# servoSchematic.net
KiCad netlist of a schematic drawn in EAGLE
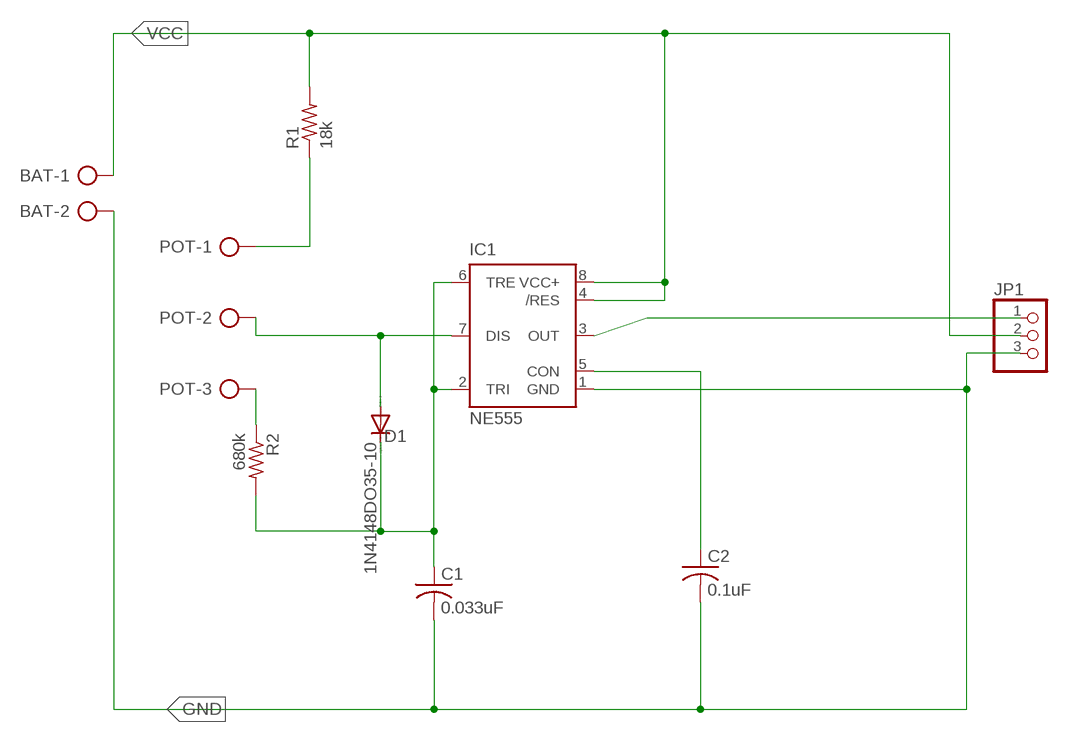
[diagram p0: schematic, sheet 1]

(export (version "E")
  (design (tool "Eeschema 10.0.6"))
  (components
    (comp (ref "BAT")
      (value "AK500/2")
      (footprint "eagle-import:AK500_2")
      (libsource (lib "eagle-import") (part "AK500/2"))
    )
    (comp (ref "C1")
      (value "0.033uF")
      (footprint "eagle-import:C025-024X044")
      (libsource (lib "eagle-import") (part "C-US025-024X044"))
    )
    (comp (ref "C2")
      (value "0.1uF")
      (footprint "eagle-import:C025-024X044")
      (libsource (lib "eagle-import") (part "C-US025-024X044"))
    )
    (comp (ref "D1")
      (value "1N4148DO35-10")
      (footprint "eagle-import:DO35-10")
      (libsource (lib "eagle-import") (part "1N4148DO35-10"))
    )
    (comp (ref "IC1")
      (value "NE555")
      (footprint "eagle-import:DIL-08")
      (fields (field (name "MF") "Arrow Electronics") (field (name "MPN") "NE555N"))
      (libsource (lib "eagle-import") (part "NE555"))
    )
    (comp (ref "JP1")
      (value "PINHD-1X3/90")
      (footprint "eagle-import:1X03_90")
      (libsource (lib "eagle-import") (part "PINHD-1X3/90"))
    )
    (comp (ref "POT")
      (value "AK500/3")
      (footprint "eagle-import:AK500_3")
      (libsource (lib "eagle-import") (part "AK500/3"))
    )
    (comp (ref "R1")
      (value "18k")
      (footprint "eagle-import:0204_7")
      (libsource (lib "eagle-import") (part "R-US_0204/7"))
    )
    (comp (ref "R2")
      (value "680k")
      (footprint "eagle-import:0204_7")
      (libsource (lib "eagle-import") (part "R-US_0204/7"))
    )
  )
  (nets
    (net (code "1") (name "GND") (class "Default")
      (node (ref "BAT") (pin "2") (pinfunction "KL_2") (pintype "passive"))
      (node (ref "C1") (pin "2") (pinfunction "2_2") (pintype "passive"))
      (node (ref "C2") (pin "2") (pinfunction "2_2") (pintype "passive"))
      (node (ref "IC1") (pin "1") (pinfunction "GND_1") (pintype "power_in"))
      (node (ref "JP1") (pin "3") (pinfunction "3_3") (pintype "passive"))
    )
    (net (code "2") (name "Net-(IC1-CON)") (class "Default")
      (node (ref "C2") (pin "1") (pinfunction "1_1") (pintype "passive"))
      (node (ref "IC1") (pin "5") (pinfunction "CON_5") (pintype "input"))
    )
    (net (code "3") (name "Net-(IC1-DIS)") (class "Default")
      (node (ref "D1") (pin "A") (pinfunction "A_A") (pintype "passive"))
      (node (ref "IC1") (pin "7") (pinfunction "DIS_7") (pintype "input"))
      (node (ref "POT") (pin "2") (pinfunction "KL_2") (pintype "passive"))
    )
    (net (code "4") (name "Net-(IC1-OUT)") (class "Default")
      (node (ref "IC1") (pin "3") (pinfunction "OUT_3") (pintype "output"))
      (node (ref "JP1") (pin "1") (pinfunction "1_1") (pintype "passive"))
    )
    (net (code "5") (name "Net-(IC1-TRE)") (class "Default")
      (node (ref "C1") (pin "1") (pinfunction "1_1") (pintype "passive"))
      (node (ref "D1") (pin "C") (pinfunction "C_C") (pintype "passive"))
      (node (ref "IC1") (pin "2") (pinfunction "TRI_2") (pintype "input"))
      (node (ref "IC1") (pin "6") (pinfunction "TRE_6") (pintype "input"))
      (node (ref "R2") (pin "2") (pinfunction "2_2") (pintype "passive"))
    )
    (net (code "6") (name "Net-(POTA-KL)") (class "Default")
      (node (ref "POT") (pin "1") (pinfunction "KL_1") (pintype "passive"))
      (node (ref "R1") (pin "1") (pinfunction "1_1") (pintype "passive"))
    )
    (net (code "7") (name "Net-(POTC-KL)") (class "Default")
      (node (ref "POT") (pin "3") (pinfunction "KL_3") (pintype "passive"))
      (node (ref "R2") (pin "1") (pinfunction "1_1") (pintype "passive"))
    )
    (net (code "8") (name "VCC") (class "Default")
      (node (ref "BAT") (pin "1") (pinfunction "KL_1") (pintype "passive"))
      (node (ref "IC1") (pin "4") (pinfunction "/RES_4") (pintype "input"))
      (node (ref "IC1") (pin "8") (pinfunction "VCC+_8") (pintype "power_in"))
      (node (ref "JP1") (pin "2") (pinfunction "2_2") (pintype "passive"))
      (node (ref "R1") (pin "2") (pinfunction "2_2") (pintype "passive"))
    )
  )
)
